# TinySpectrometer-mk-1_0.net
KiCad netlist of a schematic drawn in EAGLE
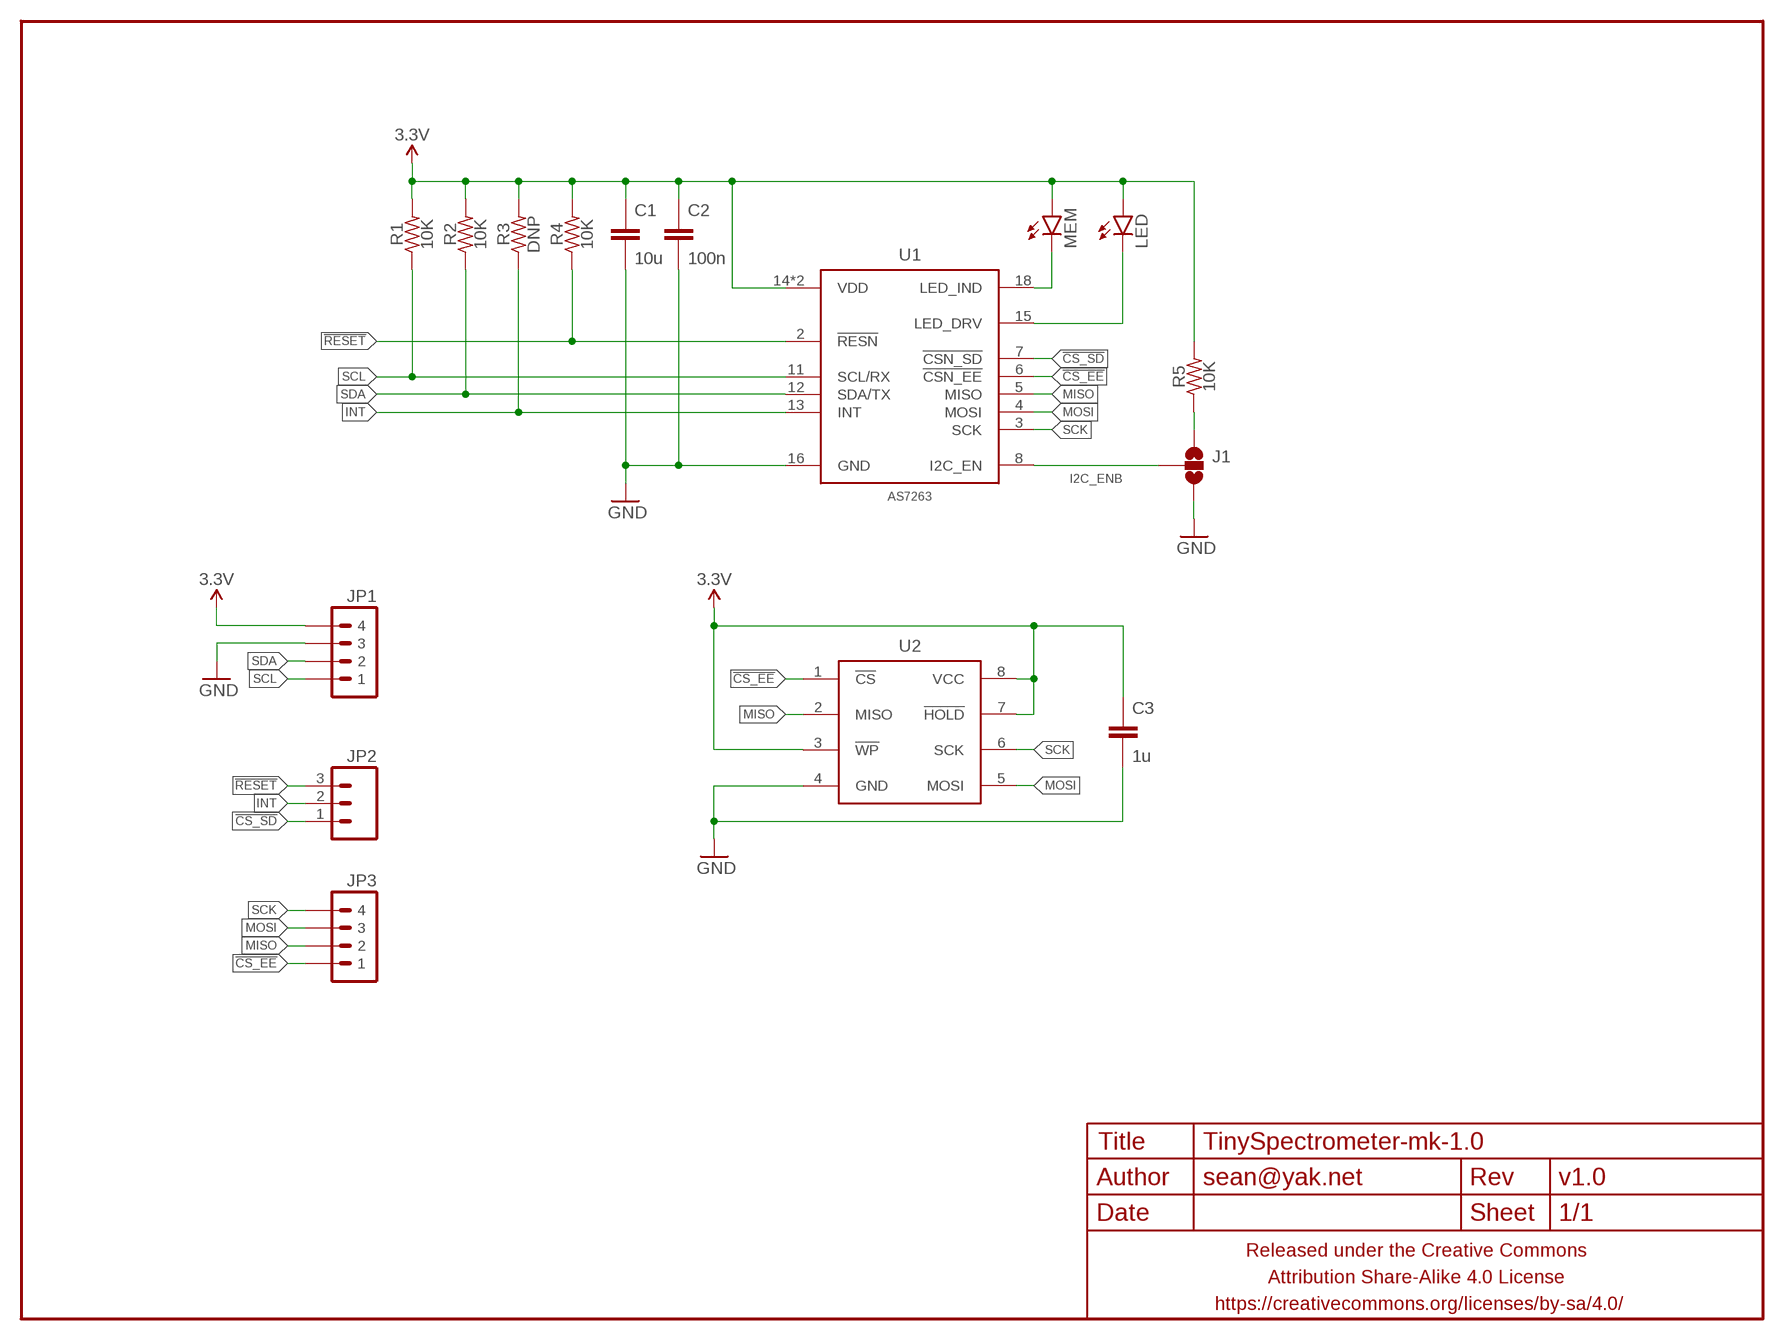
[diagram p0: schematic, sheet 1]

(export (version "E")
  (design (tool "Eeschema 10.0.6"))
  (components
    (comp (ref "C1")
      (value "10u")
      (footprint "eagle-import:C0603-TIGHTER")
      (libsource (lib "eagle-import") (part "CAPACITOR-CERAMICC0603-TIGHTER"))
    )
    (comp (ref "C2")
      (value "100n")
      (footprint "eagle-import:C0603-TIGHTER")
      (libsource (lib "eagle-import") (part "CAPACITOR-CERAMICC0603-TIGHTER"))
    )
    (comp (ref "C3")
      (value "1u")
      (footprint "eagle-import:C0603-TIGHTER")
      (libsource (lib "eagle-import") (part "CAPACITOR-CERAMICC0603-TIGHTER"))
    )
    (comp (ref "FRAME1")
      (value "FRAME-LETTERNO_PACKAGE")
      (footprint "eagle-import:DUMMY")
      (fields (field (name "DESIGNER") "sean@yak.net") (field (name "VERSION") "v1.0"))
      (libsource (lib "eagle-import") (part "FRAME-LETTERNO_PACKAGE"))
    )
    (comp (ref "J1")
      (value "JUMPER-PAD-3-NOSMALLER")
      (footprint "eagle-import:PAD-JUMPER-3-NO_YES_SILK_FULL_BOX_SMALLER")
      (libsource (lib "eagle-import") (part "JUMPER-PAD-3-NOSMALLER"))
    )
    (comp (ref "JP1")
      (value "M04PTH-CENTERED")
      (footprint "eagle-import:1X04-PTH-VERT-CENTER")
      (libsource (lib "eagle-import") (part "M04PTH-CENTERED"))
    )
    (comp (ref "JP2")
      (value "M03PTH-CENTERED")
      (footprint "eagle-import:1X03-CENTERED")
      (libsource (lib "eagle-import") (part "M03PTH-CENTERED"))
    )
    (comp (ref "JP3")
      (value "M04PTH-CENTERED")
      (footprint "eagle-import:1X04-PTH-VERT-CENTER")
      (libsource (lib "eagle-import") (part "M04PTH-CENTERED"))
    )
    (comp (ref "LED")
      (value "LED1206")
      (footprint "eagle-import:LED-1206")
      (libsource (lib "eagle-import") (part "LED1206"))
    )
    (comp (ref "MEM")
      (value "LED0603-TIGHT")
      (footprint "eagle-import:LED-0603-TIGHT")
      (libsource (lib "eagle-import") (part "LED0603-TIGHT"))
    )
    (comp (ref "R1")
      (value "10K")
      (footprint "eagle-import:R0603-TIGHTER")
      (libsource (lib "eagle-import") (part "RESISTORR0603-TIGHTER"))
    )
    (comp (ref "R2")
      (value "10K")
      (footprint "eagle-import:R0603-TIGHTER")
      (libsource (lib "eagle-import") (part "RESISTORR0603-TIGHTER"))
    )
    (comp (ref "R3")
      (value "DNP")
      (footprint "eagle-import:R0603-TIGHTER")
      (libsource (lib "eagle-import") (part "RESISTORR0603-TIGHTER"))
    )
    (comp (ref "R4")
      (value "10K")
      (footprint "eagle-import:R0603-TIGHTER")
      (libsource (lib "eagle-import") (part "RESISTORR0603-TIGHTER"))
    )
    (comp (ref "R5")
      (value "10K")
      (footprint "eagle-import:R0603-TIGHTER")
      (libsource (lib "eagle-import") (part "RESISTORR0603-TIGHTER"))
    )
    (comp (ref "U1")
      (value "AS7263")
      (footprint "eagle-import:AS7263-LGA20")
      (libsource (lib "eagle-import") (part "AS7263"))
    )
    (comp (ref "U2")
      (value "SPI_FLASHSOIC")
      (footprint "eagle-import:SO08")
      (libsource (lib "eagle-import") (part "SPI_FLASHSOIC"))
    )
  )
  (nets
    (net (code "1") (name "/I2C_ENB") (class "Default")
      (node (ref "J1") (pin "2") (pinfunction "2_2") (pintype "passive"))
      (node (ref "U1") (pin "8") (pinfunction "I2C_EN_8") (pintype "bidirectional"))
    )
    (net (code "2") (name "/~{CS_EE}") (class "Default")
      (node (ref "JP3") (pin "1") (pinfunction "1_1") (pintype "passive"))
      (node (ref "U1") (pin "6") (pinfunction "~{CSN_EE}_6") (pintype "bidirectional"))
      (node (ref "U2") (pin "1") (pinfunction "~{CS}_1") (pintype "bidirectional"))
    )
    (net (code "3") (name "/~{CS_SD}") (class "Default")
      (node (ref "JP2") (pin "1") (pinfunction "1_1") (pintype "passive"))
      (node (ref "U1") (pin "7") (pinfunction "~{CSN_SD}_7") (pintype "bidirectional"))
    )
    (net (code "4") (name "/~{RESET}") (class "Default")
      (node (ref "JP2") (pin "3") (pinfunction "3_3") (pintype "passive"))
      (node (ref "R4") (pin "1") (pinfunction "1_1") (pintype "passive"))
      (node (ref "U1") (pin "2") (pinfunction "~{RESN}_2") (pintype "bidirectional"))
    )
    (net (code "5") (name "3.3V") (class "Default")
      (node (ref "C1") (pin "1") (pinfunction "1_1") (pintype "passive"))
      (node (ref "C2") (pin "1") (pinfunction "1_1") (pintype "passive"))
      (node (ref "C3") (pin "1") (pinfunction "1_1") (pintype "passive"))
      (node (ref "JP1") (pin "4") (pinfunction "4_4") (pintype "passive"))
      (node (ref "LED") (pin "A") (pinfunction "A_A") (pintype "passive"))
      (node (ref "MEM") (pin "A") (pinfunction "A_A") (pintype "passive"))
      (node (ref "R1") (pin "2") (pinfunction "2_2") (pintype "passive"))
      (node (ref "R2") (pin "2") (pinfunction "2_2") (pintype "passive"))
      (node (ref "R3") (pin "2") (pinfunction "2_2") (pintype "passive"))
      (node (ref "R4") (pin "2") (pinfunction "2_2") (pintype "passive"))
      (node (ref "R5") (pin "2") (pinfunction "2_2") (pintype "passive"))
      (node (ref "U1") (pin "14") (pinfunction "VDD_14") (pintype "bidirectional"))
      (node (ref "U1") (pin "17") (pinfunction "VDD_17") (pintype "bidirectional"))
      (node (ref "U2") (pin "3") (pinfunction "~{WP}_3") (pintype "bidirectional"))
      (node (ref "U2") (pin "7") (pinfunction "~{HOLD}_7") (pintype "bidirectional"))
      (node (ref "U2") (pin "8") (pinfunction "VCC_8") (pintype "bidirectional"))
    )
    (net (code "6") (name "GND") (class "Default")
      (node (ref "C1") (pin "2") (pinfunction "2_2") (pintype "passive"))
      (node (ref "C2") (pin "2") (pinfunction "2_2") (pintype "passive"))
      (node (ref "C3") (pin "2") (pinfunction "2_2") (pintype "passive"))
      (node (ref "J1") (pin "3") (pinfunction "3_3") (pintype "passive"))
      (node (ref "JP1") (pin "3") (pinfunction "3_3") (pintype "passive"))
      (node (ref "U1") (pin "16") (pinfunction "GND_16") (pintype "bidirectional"))
      (node (ref "U2") (pin "4") (pinfunction "GND_4") (pintype "bidirectional"))
    )
    (net (code "7") (name "INT") (class "Default")
      (node (ref "JP2") (pin "2") (pinfunction "2_2") (pintype "passive"))
      (node (ref "R3") (pin "1") (pinfunction "1_1") (pintype "passive"))
      (node (ref "U1") (pin "13") (pinfunction "INT_13") (pintype "bidirectional"))
    )
    (net (code "8") (name "MISO") (class "Default")
      (node (ref "JP3") (pin "2") (pinfunction "2_2") (pintype "passive"))
      (node (ref "U1") (pin "5") (pinfunction "MISO_5") (pintype "bidirectional"))
      (node (ref "U2") (pin "2") (pinfunction "MISO_2") (pintype "bidirectional"))
    )
    (net (code "9") (name "MOSI") (class "Default")
      (node (ref "JP3") (pin "3") (pinfunction "3_3") (pintype "passive"))
      (node (ref "U1") (pin "4") (pinfunction "MOSI_4") (pintype "bidirectional"))
      (node (ref "U2") (pin "5") (pinfunction "MOSI_5") (pintype "bidirectional"))
    )
    (net (code "10") (name "Net-(J1-Pad1)") (class "Default")
      (node (ref "J1") (pin "1") (pinfunction "1_1") (pintype "passive"))
      (node (ref "R5") (pin "1") (pinfunction "1_1") (pintype "passive"))
    )
    (net (code "11") (name "Net-(U1-LED_DRV)") (class "Default")
      (node (ref "LED") (pin "C") (pinfunction "C_C") (pintype "passive"))
      (node (ref "U1") (pin "15") (pinfunction "LED_DRV_15") (pintype "bidirectional"))
    )
    (net (code "12") (name "Net-(U1-LED_IND)") (class "Default")
      (node (ref "MEM") (pin "C") (pinfunction "C_C") (pintype "passive"))
      (node (ref "U1") (pin "18") (pinfunction "LED_IND_18") (pintype "bidirectional"))
    )
    (net (code "13") (name "SCK") (class "Default")
      (node (ref "JP3") (pin "4") (pinfunction "4_4") (pintype "passive"))
      (node (ref "U1") (pin "3") (pinfunction "SCK_3") (pintype "bidirectional"))
      (node (ref "U2") (pin "6") (pinfunction "SCK_6") (pintype "bidirectional"))
    )
    (net (code "14") (name "SCL") (class "Default")
      (node (ref "JP1") (pin "1") (pinfunction "1_1") (pintype "passive"))
      (node (ref "R1") (pin "1") (pinfunction "1_1") (pintype "passive"))
      (node (ref "U1") (pin "11") (pinfunction "SCL/RX_11") (pintype "bidirectional"))
    )
    (net (code "15") (name "SDA") (class "Default")
      (node (ref "JP1") (pin "2") (pinfunction "2_2") (pintype "passive"))
      (node (ref "R2") (pin "1") (pinfunction "1_1") (pintype "passive"))
      (node (ref "U1") (pin "12") (pinfunction "SDA/TX_12") (pintype "bidirectional"))
    )
  )
)
